# Output.net
KiCad netlist of a schematic drawn in Altium Designer
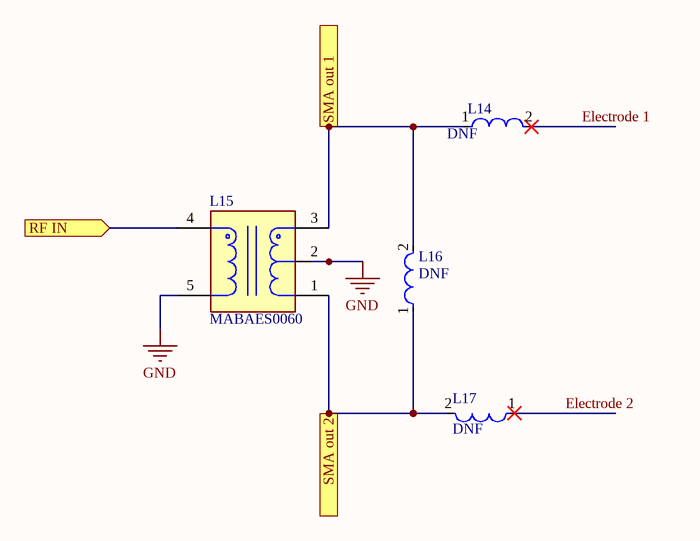
[diagram p0: Output.SchDoc]

(export (version "E")
  (design (tool "Eeschema 10.0.6"))
  (components
    (comp (ref "L14")
      (value "DNF")
      (footprint "FP-MLZ2012-1_25-IPC_C")
      (description "Shielded Multilayer Inductor 1uH ±20% 800mA 130mΩ AEC-Q200 SMD 0805")
      (fields (field (name "TOLERANCE") "20%"))
      (libsource (lib "Altium Content Vault") (part "725321dda6339637d4d059423bc1c3c"))
    )
    (comp (ref "L15")
      (value "MABAES0060")
      (footprint "FP-MABAES0060-MFG")
      (description "BALUN 300KHZ-200MHZ 1:1 6SMD")
      (libsource (lib "Altium Content Vault") (part "a416973d4767a0660ebfda87df8877f"))
    )
    (comp (ref "L16")
      (value "DNF")
      (footprint "FP-MLZ2012-1_25-IPC_C")
      (description "Shielded Multilayer Inductor 1uH ±20% 800mA 130mΩ AEC-Q200 SMD 0805")
      (fields (field (name "TOLERANCE") "20%"))
      (libsource (lib "Altium Content Vault") (part "725321dda6339637d4d059423bc1c3c"))
    )
    (comp (ref "L17")
      (value "DNF")
      (footprint "FP-MLZ2012-1_25-IPC_C")
      (description "Shielded Multilayer Inductor 1uH ±20% 800mA 130mΩ AEC-Q200 SMD 0805")
      (fields (field (name "TOLERANCE") "20%"))
      (libsource (lib "Altium Content Vault") (part "725321dda6339637d4d059423bc1c3c"))
    )
  )
  (nets
    (net (code "1") (name "/Electrode 1") (class "Default")
      (node (ref "L14") (pin "2") (pinfunction "2_2") (pintype "passive+no_connect"))
    )
    (net (code "2") (name "/Electrode 2") (class "Default")
      (node (ref "L17") (pin "1") (pinfunction "1_1") (pintype "passive+no_connect"))
    )
    (net (code "3") (name "/RF IN") (class "Default")
      (node (ref "L15") (pin "4") (pinfunction "Primary_dot_4") (pintype "passive"))
    )
    (net (code "4") (name "/SMA out 1") (class "Default")
      (node (ref "L14") (pin "1") (pinfunction "1_1") (pintype "passive"))
      (node (ref "L15") (pin "3") (pinfunction "Secondary_Dot_3") (pintype "passive"))
      (node (ref "L16") (pin "2") (pinfunction "2_2") (pintype "passive"))
    )
    (net (code "5") (name "/SMA out 2") (class "Default")
      (node (ref "L15") (pin "1") (pinfunction "Secondary_1") (pintype "passive"))
      (node (ref "L16") (pin "1") (pinfunction "1_1") (pintype "passive"))
      (node (ref "L17") (pin "2") (pinfunction "2_2") (pintype "passive"))
    )
    (net (code "6") (name "GND") (class "Default")
      (node (ref "L15") (pin "2") (pinfunction "Secondary_CT_2") (pintype "passive"))
      (node (ref "L15") (pin "5") (pinfunction "Primary_5") (pintype "passive"))
    )
  )
)
